# DC-Link-Caps.net
KiCad netlist of a schematic drawn in Altium Designer
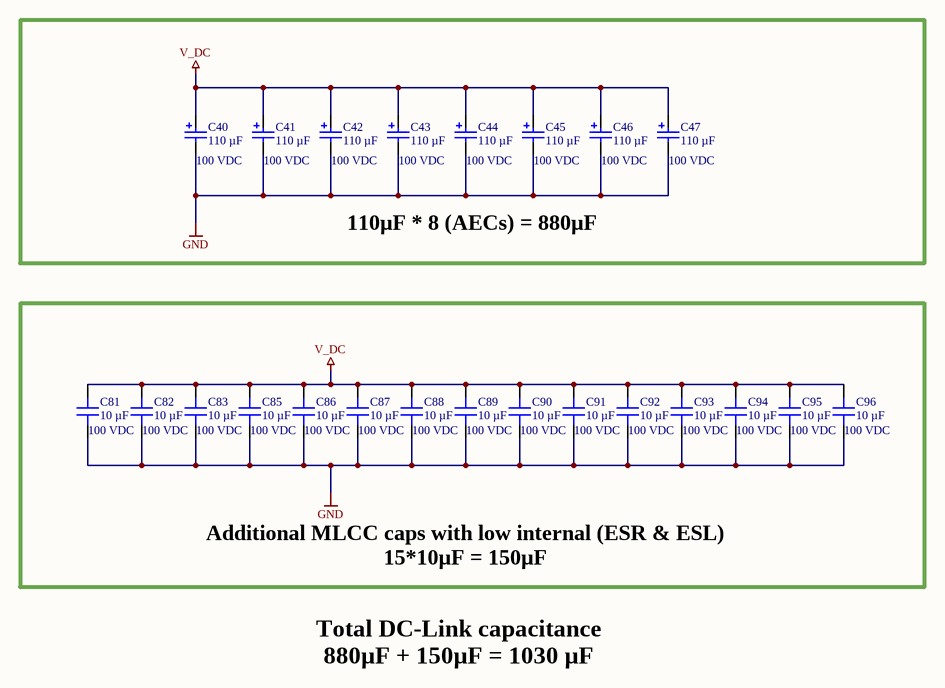
[diagram p0: DC-Link-Caps.SchDoc]

(export (version "E")
  (design (tool "Eeschema 10.0.6"))
  (components
    (comp (ref "C40")
      (value "110 µF")
      (footprint "CAPAE1300X1400N")
      (description "Capacitor, 110µF, 100VDC Al Electrolyt")
      (fields
        (field (name "MANUFACTURER PART NUMBER") "EMHS101ARA111MKE0S")
        (field (name "MANUFACTURER") "CHEMI-CON")
        (field (name "VOLTAGE RATING") "100 VDC")
        (field (name "CREATED FROM") "KPatel")
      )
      (libsource (lib "user") (part "Capacitor_Polarized"))
    )
    (comp (ref "C41")
      (value "110 µF")
      (footprint "CAPAE1300X1400N")
      (description "Capacitor, 110µF, 100VDC Al Electrolyt")
      (fields
        (field (name "MANUFACTURER PART NUMBER") "EMHS101ARA111MKE0S")
        (field (name "MANUFACTURER") "CHEMI-CON")
        (field (name "VOLTAGE RATING") "100 VDC")
        (field (name "CREATED FROM") "KPatel")
      )
      (libsource (lib "user") (part "Capacitor_Polarized"))
    )
    (comp (ref "C42")
      (value "110 µF")
      (footprint "CAPAE1300X1400N")
      (description "Capacitor, 110µF, 100VDC Al Electrolyt")
      (fields
        (field (name "MANUFACTURER PART NUMBER") "EMHS101ARA111MKE0S")
        (field (name "MANUFACTURER") "CHEMI-CON")
        (field (name "VOLTAGE RATING") "100 VDC")
        (field (name "CREATED FROM") "KPatel")
      )
      (libsource (lib "user") (part "Capacitor_Polarized"))
    )
    (comp (ref "C43")
      (value "110 µF")
      (footprint "CAPAE1300X1400N")
      (description "Capacitor, 110µF, 100VDC Al Electrolyt")
      (fields
        (field (name "MANUFACTURER PART NUMBER") "EMHS101ARA111MKE0S")
        (field (name "MANUFACTURER") "CHEMI-CON")
        (field (name "VOLTAGE RATING") "100 VDC")
        (field (name "CREATED FROM") "KPatel")
      )
      (libsource (lib "user") (part "Capacitor_Polarized"))
    )
    (comp (ref "C44")
      (value "110 µF")
      (footprint "CAPAE1300X1400N")
      (description "Capacitor, 110µF, 100VDC Al Electrolyt")
      (fields
        (field (name "MANUFACTURER PART NUMBER") "EMHS101ARA111MKE0S")
        (field (name "MANUFACTURER") "CHEMI-CON")
        (field (name "VOLTAGE RATING") "100 VDC")
        (field (name "CREATED FROM") "KPatel")
      )
      (libsource (lib "user") (part "Capacitor_Polarized"))
    )
    (comp (ref "C45")
      (value "110 µF")
      (footprint "CAPAE1300X1400N")
      (description "Capacitor, 110µF, 100VDC Al Electrolyt")
      (fields
        (field (name "MANUFACTURER PART NUMBER") "EMHS101ARA111MKE0S")
        (field (name "MANUFACTURER") "CHEMI-CON")
        (field (name "VOLTAGE RATING") "100 VDC")
        (field (name "CREATED FROM") "KPatel")
      )
      (libsource (lib "user") (part "Capacitor_Polarized"))
    )
    (comp (ref "C46")
      (value "110 µF")
      (footprint "CAPAE1300X1400N")
      (description "Capacitor, 110µF, 100VDC Al Electrolyt")
      (fields
        (field (name "MANUFACTURER PART NUMBER") "EMHS101ARA111MKE0S")
        (field (name "MANUFACTURER") "CHEMI-CON")
        (field (name "VOLTAGE RATING") "100 VDC")
        (field (name "CREATED FROM") "KPatel")
      )
      (libsource (lib "user") (part "Capacitor_Polarized"))
    )
    (comp (ref "C47")
      (value "110 µF")
      (footprint "CAPAE1300X1400N")
      (description "Capacitor, 110µF, 100VDC Al Electrolyt")
      (fields
        (field (name "MANUFACTURER PART NUMBER") "EMHS101ARA111MKE0S")
        (field (name "MANUFACTURER") "CHEMI-CON")
        (field (name "VOLTAGE RATING") "100 VDC")
        (field (name "CREATED FROM") "KPatel")
      )
      (libsource (lib "user") (part "Capacitor_Polarized"))
    )
    (comp (ref "C81")
      (value "10 µF")
      (footprint "C_1210_N")
      (description "Capacitor 1210, 100 VDC, 10µF, X7S")
      (fields
        (field (name "MANUFACTURER PART NUMBER") "GRM32EC72A106KE05L")
        (field (name "MANUFACTURER") "Murata Electronics")
        (field (name "VOLTAGE RATING") "100 VDC")
        (field (name "CREATED FROM") "DHufnagel")
      )
      (libsource (lib "user") (part "Capacitor"))
    )
    (comp (ref "C82")
      (value "10 µF")
      (footprint "C_1210_N")
      (description "Capacitor 1210, 100 VDC, 10µF, X7S")
      (fields
        (field (name "MANUFACTURER PART NUMBER") "GRM32EC72A106KE05L")
        (field (name "MANUFACTURER") "Murata Electronics")
        (field (name "VOLTAGE RATING") "100 VDC")
        (field (name "CREATED FROM") "DHufnagel")
      )
      (libsource (lib "user") (part "Capacitor"))
    )
    (comp (ref "C83")
      (value "10 µF")
      (footprint "C_1210_N")
      (description "Capacitor 1210, 100 VDC, 10µF, X7S")
      (fields
        (field (name "MANUFACTURER PART NUMBER") "GRM32EC72A106KE05L")
        (field (name "MANUFACTURER") "Murata Electronics")
        (field (name "VOLTAGE RATING") "100 VDC")
        (field (name "CREATED FROM") "DHufnagel")
      )
      (libsource (lib "user") (part "Capacitor"))
    )
    (comp (ref "C85")
      (value "10 µF")
      (footprint "C_1210_N")
      (description "Capacitor 1210, 100 VDC, 10µF, X7S")
      (fields
        (field (name "MANUFACTURER PART NUMBER") "GRM32EC72A106KE05L")
        (field (name "MANUFACTURER") "Murata Electronics")
        (field (name "VOLTAGE RATING") "100 VDC")
        (field (name "CREATED FROM") "DHufnagel")
      )
      (libsource (lib "user") (part "Capacitor"))
    )
    (comp (ref "C86")
      (value "10 µF")
      (footprint "C_1210_N")
      (description "Capacitor 1210, 100 VDC, 10µF, X7S")
      (fields
        (field (name "MANUFACTURER PART NUMBER") "GRM32EC72A106KE05L")
        (field (name "MANUFACTURER") "Murata Electronics")
        (field (name "VOLTAGE RATING") "100 VDC")
        (field (name "CREATED FROM") "DHufnagel")
      )
      (libsource (lib "user") (part "Capacitor"))
    )
    (comp (ref "C87")
      (value "10 µF")
      (footprint "C_1210_N")
      (description "Capacitor 1210, 100 VDC, 10µF, X7S")
      (fields
        (field (name "MANUFACTURER PART NUMBER") "GRM32EC72A106KE05L")
        (field (name "MANUFACTURER") "Murata Electronics")
        (field (name "VOLTAGE RATING") "100 VDC")
        (field (name "CREATED FROM") "DHufnagel")
      )
      (libsource (lib "user") (part "Capacitor"))
    )
    (comp (ref "C88")
      (value "10 µF")
      (footprint "C_1210_N")
      (description "Capacitor 1210, 100 VDC, 10µF, X7S")
      (fields
        (field (name "MANUFACTURER PART NUMBER") "GRM32EC72A106KE05L")
        (field (name "MANUFACTURER") "Murata Electronics")
        (field (name "VOLTAGE RATING") "100 VDC")
        (field (name "CREATED FROM") "DHufnagel")
      )
      (libsource (lib "user") (part "Capacitor"))
    )
    (comp (ref "C89")
      (value "10 µF")
      (footprint "C_1210_N")
      (description "Capacitor 1210, 100 VDC, 10µF, X7S")
      (fields
        (field (name "MANUFACTURER PART NUMBER") "GRM32EC72A106KE05L")
        (field (name "MANUFACTURER") "Murata Electronics")
        (field (name "VOLTAGE RATING") "100 VDC")
        (field (name "CREATED FROM") "DHufnagel")
      )
      (libsource (lib "user") (part "Capacitor"))
    )
    (comp (ref "C90")
      (value "10 µF")
      (footprint "C_1210_N")
      (description "Capacitor 1210, 100 VDC, 10µF, X7S")
      (fields
        (field (name "MANUFACTURER PART NUMBER") "GRM32EC72A106KE05L")
        (field (name "MANUFACTURER") "Murata Electronics")
        (field (name "VOLTAGE RATING") "100 VDC")
        (field (name "CREATED FROM") "DHufnagel")
      )
      (libsource (lib "user") (part "Capacitor"))
    )
    (comp (ref "C91")
      (value "10 µF")
      (footprint "C_1210_N")
      (description "Capacitor 1210, 100 VDC, 10µF, X7S")
      (fields
        (field (name "MANUFACTURER PART NUMBER") "GRM32EC72A106KE05L")
        (field (name "MANUFACTURER") "Murata Electronics")
        (field (name "VOLTAGE RATING") "100 VDC")
        (field (name "CREATED FROM") "DHufnagel")
      )
      (libsource (lib "user") (part "Capacitor"))
    )
    (comp (ref "C92")
      (value "10 µF")
      (footprint "C_1210_N")
      (description "Capacitor 1210, 100 VDC, 10µF, X7S")
      (fields
        (field (name "MANUFACTURER PART NUMBER") "GRM32EC72A106KE05L")
        (field (name "MANUFACTURER") "Murata Electronics")
        (field (name "VOLTAGE RATING") "100 VDC")
        (field (name "CREATED FROM") "DHufnagel")
      )
      (libsource (lib "user") (part "Capacitor"))
    )
    (comp (ref "C93")
      (value "10 µF")
      (footprint "C_1210_N")
      (description "Capacitor 1210, 100 VDC, 10µF, X7S")
      (fields
        (field (name "MANUFACTURER PART NUMBER") "GRM32EC72A106KE05L")
        (field (name "MANUFACTURER") "Murata Electronics")
        (field (name "VOLTAGE RATING") "100 VDC")
        (field (name "CREATED FROM") "DHufnagel")
      )
      (libsource (lib "user") (part "Capacitor"))
    )
    (comp (ref "C94")
      (value "10 µF")
      (footprint "C_1210_N")
      (description "Capacitor 1210, 100 VDC, 10µF, X7S")
      (fields
        (field (name "MANUFACTURER PART NUMBER") "GRM32EC72A106KE05L")
        (field (name "MANUFACTURER") "Murata Electronics")
        (field (name "VOLTAGE RATING") "100 VDC")
        (field (name "CREATED FROM") "DHufnagel")
      )
      (libsource (lib "user") (part "Capacitor"))
    )
    (comp (ref "C95")
      (value "10 µF")
      (footprint "C_1210_N")
      (description "Capacitor 1210, 100 VDC, 10µF, X7S")
      (fields
        (field (name "MANUFACTURER PART NUMBER") "GRM32EC72A106KE05L")
        (field (name "MANUFACTURER") "Murata Electronics")
        (field (name "VOLTAGE RATING") "100 VDC")
        (field (name "CREATED FROM") "DHufnagel")
      )
      (libsource (lib "user") (part "Capacitor"))
    )
    (comp (ref "C96")
      (value "10 µF")
      (footprint "C_1210_N")
      (description "Capacitor 1210, 100 VDC, 10µF, X7S")
      (fields
        (field (name "MANUFACTURER PART NUMBER") "GRM32EC72A106KE05L")
        (field (name "MANUFACTURER") "Murata Electronics")
        (field (name "VOLTAGE RATING") "100 VDC")
        (field (name "CREATED FROM") "DHufnagel")
      )
      (libsource (lib "user") (part "Capacitor"))
    )
  )
  (nets
    (net (code "1") (name "GND") (class "Default")
      (node (ref "C40") (pin "2") (pinfunction "N_2") (pintype "passive"))
      (node (ref "C41") (pin "2") (pinfunction "N_2") (pintype "passive"))
      (node (ref "C42") (pin "2") (pinfunction "N_2") (pintype "passive"))
      (node (ref "C43") (pin "2") (pinfunction "N_2") (pintype "passive"))
      (node (ref "C44") (pin "2") (pinfunction "N_2") (pintype "passive"))
      (node (ref "C45") (pin "2") (pinfunction "N_2") (pintype "passive"))
      (node (ref "C46") (pin "2") (pinfunction "N_2") (pintype "passive"))
      (node (ref "C47") (pin "2") (pinfunction "N_2") (pintype "passive"))
      (node (ref "C81") (pin "1") (pinfunction "1_1") (pintype "passive"))
      (node (ref "C82") (pin "1") (pinfunction "1_1") (pintype "passive"))
      (node (ref "C83") (pin "1") (pinfunction "1_1") (pintype "passive"))
      (node (ref "C85") (pin "1") (pinfunction "1_1") (pintype "passive"))
      (node (ref "C86") (pin "1") (pinfunction "1_1") (pintype "passive"))
      (node (ref "C87") (pin "1") (pinfunction "1_1") (pintype "passive"))
      (node (ref "C88") (pin "1") (pinfunction "1_1") (pintype "passive"))
      (node (ref "C89") (pin "1") (pinfunction "1_1") (pintype "passive"))
      (node (ref "C90") (pin "1") (pinfunction "1_1") (pintype "passive"))
      (node (ref "C91") (pin "1") (pinfunction "1_1") (pintype "passive"))
      (node (ref "C92") (pin "1") (pinfunction "1_1") (pintype "passive"))
      (node (ref "C93") (pin "1") (pinfunction "1_1") (pintype "passive"))
      (node (ref "C94") (pin "1") (pinfunction "1_1") (pintype "passive"))
      (node (ref "C95") (pin "1") (pinfunction "1_1") (pintype "passive"))
      (node (ref "C96") (pin "1") (pinfunction "1_1") (pintype "passive"))
    )
    (net (code "2") (name "V_DC") (class "Default")
      (node (ref "C40") (pin "1") (pinfunction "P_1") (pintype "passive"))
      (node (ref "C41") (pin "1") (pinfunction "P_1") (pintype "passive"))
      (node (ref "C42") (pin "1") (pinfunction "P_1") (pintype "passive"))
      (node (ref "C43") (pin "1") (pinfunction "P_1") (pintype "passive"))
      (node (ref "C44") (pin "1") (pinfunction "P_1") (pintype "passive"))
      (node (ref "C45") (pin "1") (pinfunction "P_1") (pintype "passive"))
      (node (ref "C46") (pin "1") (pinfunction "P_1") (pintype "passive"))
      (node (ref "C47") (pin "1") (pinfunction "P_1") (pintype "passive"))
      (node (ref "C81") (pin "2") (pinfunction "2_2") (pintype "passive"))
      (node (ref "C82") (pin "2") (pinfunction "2_2") (pintype "passive"))
      (node (ref "C83") (pin "2") (pinfunction "2_2") (pintype "passive"))
      (node (ref "C85") (pin "2") (pinfunction "2_2") (pintype "passive"))
      (node (ref "C86") (pin "2") (pinfunction "2_2") (pintype "passive"))
      (node (ref "C87") (pin "2") (pinfunction "2_2") (pintype "passive"))
      (node (ref "C88") (pin "2") (pinfunction "2_2") (pintype "passive"))
      (node (ref "C89") (pin "2") (pinfunction "2_2") (pintype "passive"))
      (node (ref "C90") (pin "2") (pinfunction "2_2") (pintype "passive"))
      (node (ref "C91") (pin "2") (pinfunction "2_2") (pintype "passive"))
      (node (ref "C92") (pin "2") (pinfunction "2_2") (pintype "passive"))
      (node (ref "C93") (pin "2") (pinfunction "2_2") (pintype "passive"))
      (node (ref "C94") (pin "2") (pinfunction "2_2") (pintype "passive"))
      (node (ref "C95") (pin "2") (pinfunction "2_2") (pintype "passive"))
      (node (ref "C96") (pin "2") (pinfunction "2_2") (pintype "passive"))
    )
  )
)
